# Chime_PCB_v2_2.net
KiCad netlist of a schematic drawn in EAGLE
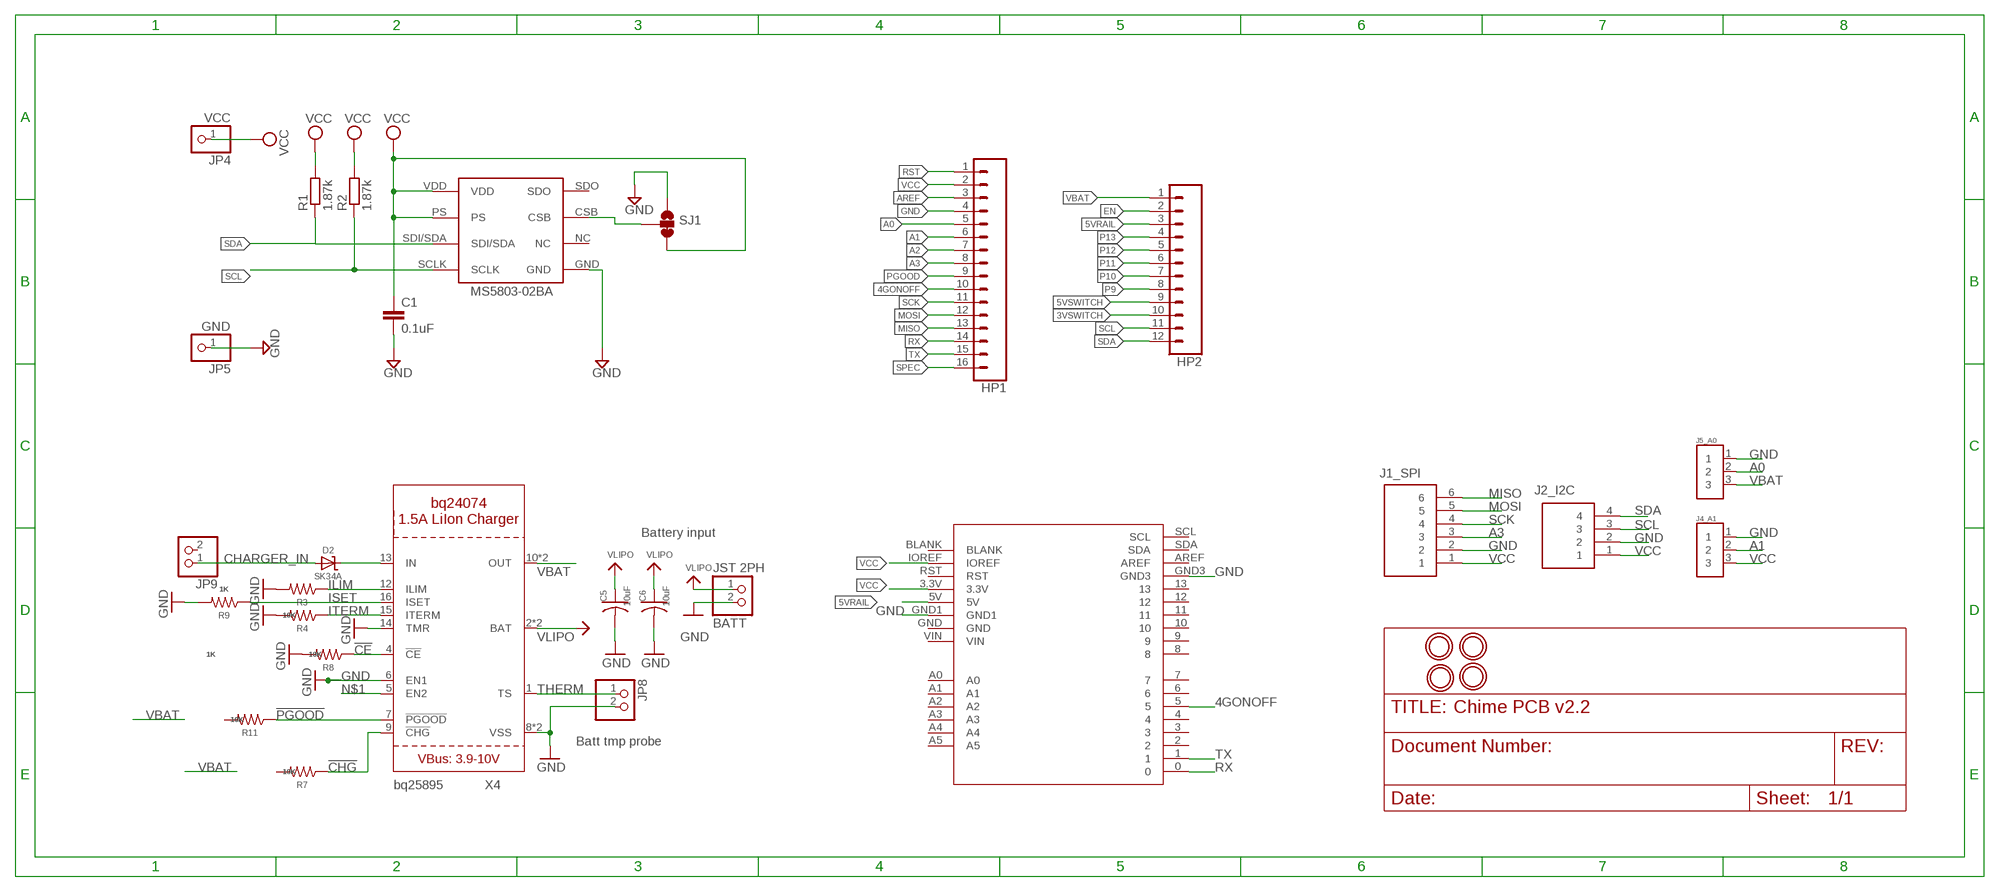
[diagram p0: schematic, sheet 1]

(export (version "E")
  (design (tool "Eeschema 10.0.6"))
  (components
    (comp (ref "BATT")
      (value "JST 2PH")
      (footprint "eagle-import:JST-PH-2-SMT-RA")
      (libsource (lib "eagle-import") (part "JST_2PIN-SMT-RA"))
    )
    (comp (ref "C1")
      (value "0.1uF")
      (footprint "eagle-import:C0805")
      (libsource (lib "eagle-import") (part "C-EUC0805"))
    )
    (comp (ref "C5")
      (value "10uF")
      (footprint "eagle-import:C0805K")
      (libsource (lib "eagle-import") (part "C-USC0805K"))
    )
    (comp (ref "C6")
      (value "10uF")
      (footprint "eagle-import:C0805K")
      (libsource (lib "eagle-import") (part "C-USC0805K"))
    )
    (comp (ref "D2")
      (value "SK34A")
      (footprint "eagle-import:SMADIODE")
      (libsource (lib "eagle-import") (part "DIODE-SCHOTTKYSMA"))
    )
    (comp (ref "HP1")
      (value "CONN_16")
      (footprint "eagle-import:1X16")
      (libsource (lib "eagle-import") (part "CONN_16"))
    )
    (comp (ref "HP2")
      (value "CONN_12")
      (footprint "eagle-import:1X12")
      (libsource (lib "eagle-import") (part "CONN_12"))
    )
    (comp (ref "J1_SPI")
      (value "1725698")
      (footprint "eagle-import:1725698")
      (fields (field (name "MOUSER_PART_NUMBER") "651-1725698"))
      (libsource (lib "eagle-import") (part "1725698"))
    )
    (comp (ref "J2_I2C")
      (value "1725672")
      (footprint "eagle-import:1725672")
      (fields (field (name "MOUSER_PART_NUMBER") "651-1725672"))
      (libsource (lib "eagle-import") (part "1725672"))
    )
    (comp (ref "J4_A1")
      (value "282834-3")
      (footprint "eagle-import:TE_282834-3")
      (fields (field (name "MF") "TE Connectivity"))
      (libsource (lib "eagle-import") (part "282834-3"))
    )
    (comp (ref "J5_A0")
      (value "282834-3")
      (footprint "eagle-import:TE_282834-3")
      (fields (field (name "MF") "TE Connectivity"))
      (libsource (lib "eagle-import") (part "282834-3"))
    )
    (comp (ref "JP4")
      (value "VCC")
      (footprint "eagle-import:1X01")
      (libsource (lib "eagle-import") (part "PINHD-1X1"))
    )
    (comp (ref "JP5")
      (value "GND")
      (footprint "eagle-import:1X01")
      (libsource (lib "eagle-import") (part "PINHD-1X1"))
    )
    (comp (ref "JP8")
      (value "PINHD-1X2")
      (footprint "eagle-import:1X02")
      (libsource (lib "eagle-import") (part "PINHD-1X2"))
    )
    (comp (ref "JP9")
      (value "PINHD-1X2")
      (footprint "eagle-import:1X02")
      (libsource (lib "eagle-import") (part "PINHD-1X2"))
    )
    (comp (ref "R1")
      (value "1.87k")
      (footprint "eagle-import:R0805")
      (libsource (lib "eagle-import") (part "R-EU_R0805"))
    )
    (comp (ref "R2")
      (value "1.87k")
      (footprint "eagle-import:R0805")
      (libsource (lib "eagle-import") (part "R-EU_R0805"))
    )
    (comp (ref "R3")
      (value "1K")
      (footprint "eagle-import:M0805")
      (libsource (lib "eagle-import") (part "R-US_M0805"))
    )
    (comp (ref "R4")
      (value "10K")
      (footprint "eagle-import:M0805")
      (libsource (lib "eagle-import") (part "R-US_M0805"))
    )
    (comp (ref "R7")
      (value "10K")
      (footprint "eagle-import:M0805")
      (libsource (lib "eagle-import") (part "R-US_M0805"))
    )
    (comp (ref "R8")
      (value "10K")
      (footprint "eagle-import:M0805")
      (libsource (lib "eagle-import") (part "R-US_M0805"))
    )
    (comp (ref "R9")
      (value "1K")
      (footprint "eagle-import:M0805")
      (libsource (lib "eagle-import") (part "R-US_M0805"))
    )
    (comp (ref "R11")
      (value "10K")
      (footprint "eagle-import:M0805")
      (libsource (lib "eagle-import") (part "R-US_M0805"))
    )
    (comp (ref "SJ1")
      (value "JUMPER-SMT_3_1-NC_TRACE_SILK")
      (footprint "eagle-import:SMT-JUMPER_3_1-NC_TRACE_SILK")
      (libsource (lib "eagle-import") (part "JUMPER-SMT_3_1-NC_TRACE_SILK"))
    )
    (comp (ref "U$1")
      (value "LTE_BOARD")
      (footprint "eagle-import:LTE_BOARD_FOOTPRINT")
      (libsource (lib "eagle-import") (part "LTE_BOARD"))
    )
    (comp (ref "U$2")
      (value "MOUNTINGHOLE2.5")
      (footprint "eagle-import:MOUNTINGHOLE_2.5_PLATED")
      (libsource (lib "eagle-import") (part "MOUNTINGHOLE2.5"))
    )
    (comp (ref "U$3")
      (value "MOUNTINGHOLE2.5")
      (footprint "eagle-import:MOUNTINGHOLE_2.5_PLATED")
      (libsource (lib "eagle-import") (part "MOUNTINGHOLE2.5"))
    )
    (comp (ref "U$4")
      (value "MOUNTINGHOLE2.5")
      (footprint "eagle-import:MOUNTINGHOLE_2.5_PLATED")
      (libsource (lib "eagle-import") (part "MOUNTINGHOLE2.5"))
    )
    (comp (ref "U$5")
      (value "MOUNTINGHOLE2.5")
      (footprint "eagle-import:MOUNTINGHOLE_2.5_PLATED")
      (libsource (lib "eagle-import") (part "MOUNTINGHOLE2.5"))
    )
    (comp (ref "U1")
      (value "MS5803-02BA")
      (footprint "eagle-import:MS5803-02BA")
      (libsource (lib "eagle-import") (part "MS5803-02BA"))
    )
    (comp (ref "X4")
      (value "BQ24074")
      (footprint "eagle-import:QFN16_3MM")
      (libsource (lib "eagle-import") (part "BQ24074"))
    )
  )
  (nets
    (net (code "1") (name "/CHARGER_IN") (class "Default")
      (node (ref "D2") (pin "A") (pinfunction "A_A") (pintype "passive"))
      (node (ref "JP9") (pin "1") (pinfunction "1_1") (pintype "passive"))
    )
    (net (code "2") (name "/ILIM") (class "Default")
      (node (ref "R3") (pin "1") (pinfunction "1_1") (pintype "passive"))
      (node (ref "X4") (pin "12") (pinfunction "ILIM_12") (pintype "input"))
    )
    (net (code "3") (name "/ISET") (class "Default")
      (node (ref "R9") (pin "1") (pinfunction "1_1") (pintype "passive"))
      (node (ref "X4") (pin "16") (pinfunction "ISET_16") (pintype "input"))
    )
    (net (code "4") (name "/ITERM") (class "Default")
      (node (ref "R4") (pin "1") (pinfunction "1_1") (pintype "passive"))
      (node (ref "X4") (pin "15") (pinfunction "ITERM_15") (pintype "input"))
    )
    (net (code "5") (name "/N$1") (class "Default")
      (node (ref "X4") (pin "5") (pinfunction "EN2_5") (pintype "input"))
    )
    (net (code "6") (name "/THERM") (class "Default")
      (node (ref "JP8") (pin "1") (pinfunction "1_1") (pintype "passive"))
      (node (ref "X4") (pin "1") (pinfunction "TS_1") (pintype "input"))
    )
    (net (code "7") (name "/~{CE}") (class "Default")
      (node (ref "R8") (pin "1") (pinfunction "1_1") (pintype "passive"))
      (node (ref "X4") (pin "4") (pinfunction "~{CE}_4") (pintype "input"))
    )
    (net (code "8") (name "/~{CHG}") (class "Default")
      (node (ref "R7") (pin "1") (pinfunction "1_1") (pintype "passive"))
      (node (ref "X4") (pin "9") (pinfunction "~{CHG}_9") (pintype "output"))
    )
    (net (code "9") (name "/~{PGOOD}") (class "Default")
      (node (ref "R11") (pin "1") (pinfunction "1_1") (pintype "passive"))
      (node (ref "X4") (pin "7") (pinfunction "~{PGOOD}_7") (pintype "output"))
    )
    (net (code "10") (name "3VSWITCH") (class "Default")
      (node (ref "HP2") (pin "10") (pinfunction "10_10") (pintype "passive"))
    )
    (net (code "11") (name "4GONOFF") (class "Default")
      (node (ref "HP1") (pin "10") (pinfunction "10_10") (pintype "passive"))
      (node (ref "U$1") (pin "5") (pinfunction "5_5") (pintype "bidirectional"))
    )
    (net (code "12") (name "5VRAIL") (class "Default")
      (node (ref "HP2") (pin "3") (pinfunction "3_3") (pintype "passive"))
      (node (ref "U$1") (pin "5V") (pinfunction "5V_5V") (pintype "bidirectional"))
    )
    (net (code "13") (name "5VSWITCH") (class "Default")
      (node (ref "HP2") (pin "9") (pinfunction "9_9") (pintype "passive"))
    )
    (net (code "14") (name "A0") (class "Default")
      (node (ref "HP1") (pin "5") (pinfunction "5_5") (pintype "passive"))
      (node (ref "J5_A0") (pin "2") (pinfunction "2_2") (pintype "passive"))
    )
    (net (code "15") (name "A1") (class "Default")
      (node (ref "HP1") (pin "6") (pinfunction "6_6") (pintype "passive"))
      (node (ref "J4_A1") (pin "2") (pinfunction "2_2") (pintype "passive"))
    )
    (net (code "16") (name "A2") (class "Default")
      (node (ref "HP1") (pin "7") (pinfunction "7_7") (pintype "passive"))
    )
    (net (code "17") (name "A3") (class "Default")
      (node (ref "HP1") (pin "8") (pinfunction "8_8") (pintype "passive"))
      (node (ref "J1_SPI") (pin "3") (pinfunction "3_3") (pintype "bidirectional"))
    )
    (net (code "18") (name "AREF") (class "Default")
      (node (ref "HP1") (pin "3") (pinfunction "3_3") (pintype "passive"))
    )
    (net (code "19") (name "EN") (class "Default")
      (node (ref "HP2") (pin "2") (pinfunction "2_2") (pintype "passive"))
    )
    (net (code "20") (name "GND") (class "Default")
      (node (ref "BATT") (pin "2") (pinfunction "1_2") (pintype "passive"))
      (node (ref "C1") (pin "2") (pinfunction "2_2") (pintype "passive"))
      (node (ref "C5") (pin "2") (pinfunction "2_2") (pintype "passive"))
      (node (ref "C6") (pin "2") (pinfunction "2_2") (pintype "passive"))
      (node (ref "HP1") (pin "4") (pinfunction "4_4") (pintype "passive"))
      (node (ref "J1_SPI") (pin "2") (pinfunction "2_2") (pintype "bidirectional"))
      (node (ref "J2_I2C") (pin "2") (pinfunction "2_2") (pintype "bidirectional"))
      (node (ref "J4_A1") (pin "1") (pinfunction "1_1") (pintype "passive"))
      (node (ref "J5_A0") (pin "1") (pinfunction "1_1") (pintype "passive"))
      (node (ref "JP5") (pin "1") (pinfunction "1_1") (pintype "passive"))
      (node (ref "JP8") (pin "2") (pinfunction "2_2") (pintype "passive"))
      (node (ref "R3") (pin "2") (pinfunction "2_2") (pintype "passive"))
      (node (ref "R4") (pin "2") (pinfunction "2_2") (pintype "passive"))
      (node (ref "R8") (pin "2") (pinfunction "2_2") (pintype "passive"))
      (node (ref "R9") (pin "2") (pinfunction "2_2") (pintype "passive"))
      (node (ref "SJ1") (pin "1") (pinfunction "1_1") (pintype "passive"))
      (node (ref "U$1") (pin "GND1") (pinfunction "GND1_GND1") (pintype "bidirectional"))
      (node (ref "U$1") (pin "GND3") (pinfunction "GND3_GND3") (pintype "bidirectional"))
      (node (ref "U1") (pin "GND") (pinfunction "GND_GND") (pintype "bidirectional"))
      (node (ref "X4") (pin "14") (pinfunction "TMR_14") (pintype "input"))
      (node (ref "X4") (pin "6") (pinfunction "EN1_6") (pintype "input"))
      (node (ref "X4") (pin "8") (pinfunction "VSS_8") (pintype "power_in"))
      (node (ref "X4") (pin "THERMAL") (pinfunction "VSS_THERMAL") (pintype "power_in"))
    )
    (net (code "21") (name "MISO") (class "Default")
      (node (ref "HP1") (pin "13") (pinfunction "13_13") (pintype "passive"))
      (node (ref "J1_SPI") (pin "6") (pinfunction "6_6") (pintype "bidirectional"))
    )
    (net (code "22") (name "MOSI") (class "Default")
      (node (ref "HP1") (pin "12") (pinfunction "12_12") (pintype "passive"))
      (node (ref "J1_SPI") (pin "5") (pinfunction "5_5") (pintype "bidirectional"))
    )
    (net (code "23") (name "Net-(SJ1-Pad2)") (class "Default")
      (node (ref "SJ1") (pin "2") (pinfunction "2_2") (pintype "passive"))
      (node (ref "U1") (pin "CSB") (pinfunction "CSB_CSB") (pintype "bidirectional"))
    )
    (net (code "24") (name "Net-(X4-IN)") (class "Default")
      (node (ref "D2") (pin "C") (pinfunction "C_C") (pintype "passive"))
      (node (ref "X4") (pin "13") (pinfunction "IN_13") (pintype "power_in"))
    )
    (net (code "25") (name "P9") (class "Default")
      (node (ref "HP2") (pin "8") (pinfunction "8_8") (pintype "passive"))
    )
    (net (code "26") (name "P10") (class "Default")
      (node (ref "HP2") (pin "7") (pinfunction "7_7") (pintype "passive"))
    )
    (net (code "27") (name "P11") (class "Default")
      (node (ref "HP2") (pin "6") (pinfunction "6_6") (pintype "passive"))
    )
    (net (code "28") (name "P12") (class "Default")
      (node (ref "HP2") (pin "5") (pinfunction "5_5") (pintype "passive"))
    )
    (net (code "29") (name "P13") (class "Default")
      (node (ref "HP2") (pin "4") (pinfunction "4_4") (pintype "passive"))
    )
    (net (code "30") (name "PGOOD") (class "Default")
      (node (ref "HP1") (pin "9") (pinfunction "9_9") (pintype "passive"))
    )
    (net (code "31") (name "RST") (class "Default")
      (node (ref "HP1") (pin "1") (pinfunction "1_1") (pintype "passive"))
    )
    (net (code "32") (name "RX") (class "Default")
      (node (ref "HP1") (pin "14") (pinfunction "14_14") (pintype "passive"))
      (node (ref "U$1") (pin "0") (pinfunction "0_0") (pintype "bidirectional"))
    )
    (net (code "33") (name "SCK") (class "Default")
      (node (ref "HP1") (pin "11") (pinfunction "11_11") (pintype "passive"))
      (node (ref "J1_SPI") (pin "4") (pinfunction "4_4") (pintype "bidirectional"))
    )
    (net (code "34") (name "SCL") (class "Default")
      (node (ref "HP2") (pin "11") (pinfunction "11_11") (pintype "passive"))
      (node (ref "J2_I2C") (pin "3") (pinfunction "3_3") (pintype "bidirectional"))
      (node (ref "R2") (pin "1") (pinfunction "1_1") (pintype "passive"))
      (node (ref "U1") (pin "SCLK") (pinfunction "SCLK_SCLK") (pintype "bidirectional"))
    )
    (net (code "35") (name "SDA") (class "Default")
      (node (ref "HP2") (pin "12") (pinfunction "12_12") (pintype "passive"))
      (node (ref "J2_I2C") (pin "4") (pinfunction "4_4") (pintype "bidirectional"))
      (node (ref "R1") (pin "1") (pinfunction "1_1") (pintype "passive"))
      (node (ref "U1") (pin "SDI/SDA") (pinfunction "SDI/SDA_SDI/SDA") (pintype "bidirectional"))
    )
    (net (code "36") (name "SPEC") (class "Default")
      (node (ref "HP1") (pin "16") (pinfunction "16_16") (pintype "passive"))
    )
    (net (code "37") (name "TX") (class "Default")
      (node (ref "HP1") (pin "15") (pinfunction "15_15") (pintype "passive"))
      (node (ref "U$1") (pin "1") (pinfunction "1_1") (pintype "bidirectional"))
    )
    (net (code "38") (name "VBAT") (class "Default")
      (node (ref "HP2") (pin "1") (pinfunction "1_1") (pintype "passive"))
      (node (ref "J5_A0") (pin "3") (pinfunction "3_3") (pintype "passive"))
      (node (ref "X4") (pin "10") (pinfunction "OUT_10") (pintype "output"))
      (node (ref "X4") (pin "11") (pinfunction "OUT_11") (pintype "output"))
    )
    (net (code "39") (name "VCC") (class "Default")
      (node (ref "C1") (pin "1") (pinfunction "1_1") (pintype "passive"))
      (node (ref "HP1") (pin "2") (pinfunction "2_2") (pintype "passive"))
      (node (ref "J1_SPI") (pin "1") (pinfunction "1_1") (pintype "bidirectional"))
      (node (ref "J2_I2C") (pin "1") (pinfunction "1_1") (pintype "bidirectional"))
      (node (ref "J4_A1") (pin "3") (pinfunction "3_3") (pintype "passive"))
      (node (ref "JP4") (pin "1") (pinfunction "1_1") (pintype "passive"))
      (node (ref "R1") (pin "2") (pinfunction "2_2") (pintype "passive"))
      (node (ref "R2") (pin "2") (pinfunction "2_2") (pintype "passive"))
      (node (ref "SJ1") (pin "3") (pinfunction "3_3") (pintype "passive"))
      (node (ref "U$1") (pin "3.3V") (pinfunction "3.3V_3.3V") (pintype "bidirectional"))
      (node (ref "U$1") (pin "IOREF") (pinfunction "IOREF_IOREF") (pintype "bidirectional"))
      (node (ref "U1") (pin "PS") (pinfunction "PS_PS") (pintype "bidirectional"))
      (node (ref "U1") (pin "VDD") (pinfunction "VDD_VDD") (pintype "bidirectional"))
    )
    (net (code "40") (name "VLIPO") (class "Default")
      (node (ref "BATT") (pin "1") (pinfunction "2_1") (pintype "passive"))
      (node (ref "C5") (pin "1") (pinfunction "1_1") (pintype "passive"))
      (node (ref "C6") (pin "1") (pinfunction "1_1") (pintype "passive"))
      (node (ref "X4") (pin "2") (pinfunction "BAT_2") (pintype "input"))
      (node (ref "X4") (pin "3") (pinfunction "BAT_3") (pintype "input"))
    )
    (net (code "41") (name "unconnected-(JP9-Pad2)") (class "Default")
      (node (ref "JP9") (pin "2") (pinfunction "2_2") (pintype "passive"))
    )
    (net (code "42") (name "unconnected-(R7-Pad2)") (class "Default")
      (node (ref "R7") (pin "2") (pinfunction "2_2") (pintype "passive"))
    )
    (net (code "43") (name "unconnected-(R11-Pad2)") (class "Default")
      (node (ref "R11") (pin "2") (pinfunction "2_2") (pintype "passive"))
    )
    (net (code "44") (name "unconnected-(U$1-Pad2)") (class "Default")
      (node (ref "U$1") (pin "2") (pinfunction "2_2") (pintype "bidirectional"))
    )
    (net (code "45") (name "unconnected-(U$1-Pad3)") (class "Default")
      (node (ref "U$1") (pin "3") (pinfunction "3_3") (pintype "bidirectional"))
    )
    (net (code "46") (name "unconnected-(U$1-Pad4)") (class "Default")
      (node (ref "U$1") (pin "4") (pinfunction "4_4") (pintype "bidirectional"))
    )
    (net (code "47") (name "unconnected-(U$1-Pad6)") (class "Default")
      (node (ref "U$1") (pin "6") (pinfunction "6_6") (pintype "bidirectional"))
    )
    (net (code "48") (name "unconnected-(U$1-Pad7)") (class "Default")
      (node (ref "U$1") (pin "7") (pinfunction "7_7") (pintype "bidirectional"))
    )
    (net (code "49") (name "unconnected-(U$1-Pad8)") (class "Default")
      (node (ref "U$1") (pin "8") (pinfunction "8_8") (pintype "bidirectional"))
    )
    (net (code "50") (name "unconnected-(U$1-Pad9)") (class "Default")
      (node (ref "U$1") (pin "9") (pinfunction "9_9") (pintype "bidirectional"))
    )
    (net (code "51") (name "unconnected-(U$1-Pad10)") (class "Default")
      (node (ref "U$1") (pin "10") (pinfunction "10_10") (pintype "bidirectional"))
    )
    (net (code "52") (name "unconnected-(U$1-Pad11)") (class "Default")
      (node (ref "U$1") (pin "11") (pinfunction "11_11") (pintype "bidirectional"))
    )
    (net (code "53") (name "unconnected-(U$1-Pad12)") (class "Default")
      (node (ref "U$1") (pin "12") (pinfunction "12_12") (pintype "bidirectional"))
    )
    (net (code "54") (name "unconnected-(U$1-Pad13)") (class "Default")
      (node (ref "U$1") (pin "13") (pinfunction "13_13") (pintype "bidirectional"))
    )
    (net (code "55") (name "unconnected-(U$1-PadA0)") (class "Default")
      (node (ref "U$1") (pin "A0") (pinfunction "A0_A0") (pintype "bidirectional"))
    )
    (net (code "56") (name "unconnected-(U$1-PadA1)") (class "Default")
      (node (ref "U$1") (pin "A1") (pinfunction "A1_A1") (pintype "bidirectional"))
    )
    (net (code "57") (name "unconnected-(U$1-PadA2)") (class "Default")
      (node (ref "U$1") (pin "A2") (pinfunction "A2_A2") (pintype "bidirectional"))
    )
    (net (code "58") (name "unconnected-(U$1-PadA3)") (class "Default")
      (node (ref "U$1") (pin "A3") (pinfunction "A3_A3") (pintype "bidirectional"))
    )
    (net (code "59") (name "unconnected-(U$1-PadA4)") (class "Default")
      (node (ref "U$1") (pin "A4") (pinfunction "A4_A4") (pintype "bidirectional"))
    )
    (net (code "60") (name "unconnected-(U$1-PadA5)") (class "Default")
      (node (ref "U$1") (pin "A5") (pinfunction "A5_A5") (pintype "bidirectional"))
    )
    (net (code "61") (name "unconnected-(U$1-PadAREF)") (class "Default")
      (node (ref "U$1") (pin "AREF") (pinfunction "AREF_AREF") (pintype "bidirectional"))
    )
    (net (code "62") (name "unconnected-(U$1-PadBLANK)") (class "Default")
      (node (ref "U$1") (pin "BLANK") (pinfunction "BLANK_BLANK") (pintype "bidirectional"))
    )
    (net (code "63") (name "unconnected-(U$1-PadGND)") (class "Default")
      (node (ref "U$1") (pin "GND") (pinfunction "GND_GND") (pintype "bidirectional"))
    )
    (net (code "64") (name "unconnected-(U$1-PadRST)") (class "Default")
      (node (ref "U$1") (pin "RST") (pinfunction "RST_RST") (pintype "bidirectional"))
    )
    (net (code "65") (name "unconnected-(U$1-PadSCL)") (class "Default")
      (node (ref "U$1") (pin "SCL") (pinfunction "SCL_SCL") (pintype "bidirectional"))
    )
    (net (code "66") (name "unconnected-(U$1-PadSDA)") (class "Default")
      (node (ref "U$1") (pin "SDA") (pinfunction "SDA_SDA") (pintype "bidirectional"))
    )
    (net (code "67") (name "unconnected-(U$1-PadVIN)") (class "Default")
      (node (ref "U$1") (pin "VIN") (pinfunction "VIN_VIN") (pintype "bidirectional"))
    )
    (net (code "68") (name "unconnected-(U1-PadNC)") (class "Default")
      (node (ref "U1") (pin "NC") (pinfunction "NC_NC") (pintype "bidirectional"))
    )
    (net (code "69") (name "unconnected-(U1-PadSDO)") (class "Default")
      (node (ref "U1") (pin "SDO") (pinfunction "SDO_SDO") (pintype "bidirectional"))
    )
  )
)
